# Main.net
KiCad netlist of a schematic drawn in Altium Designer
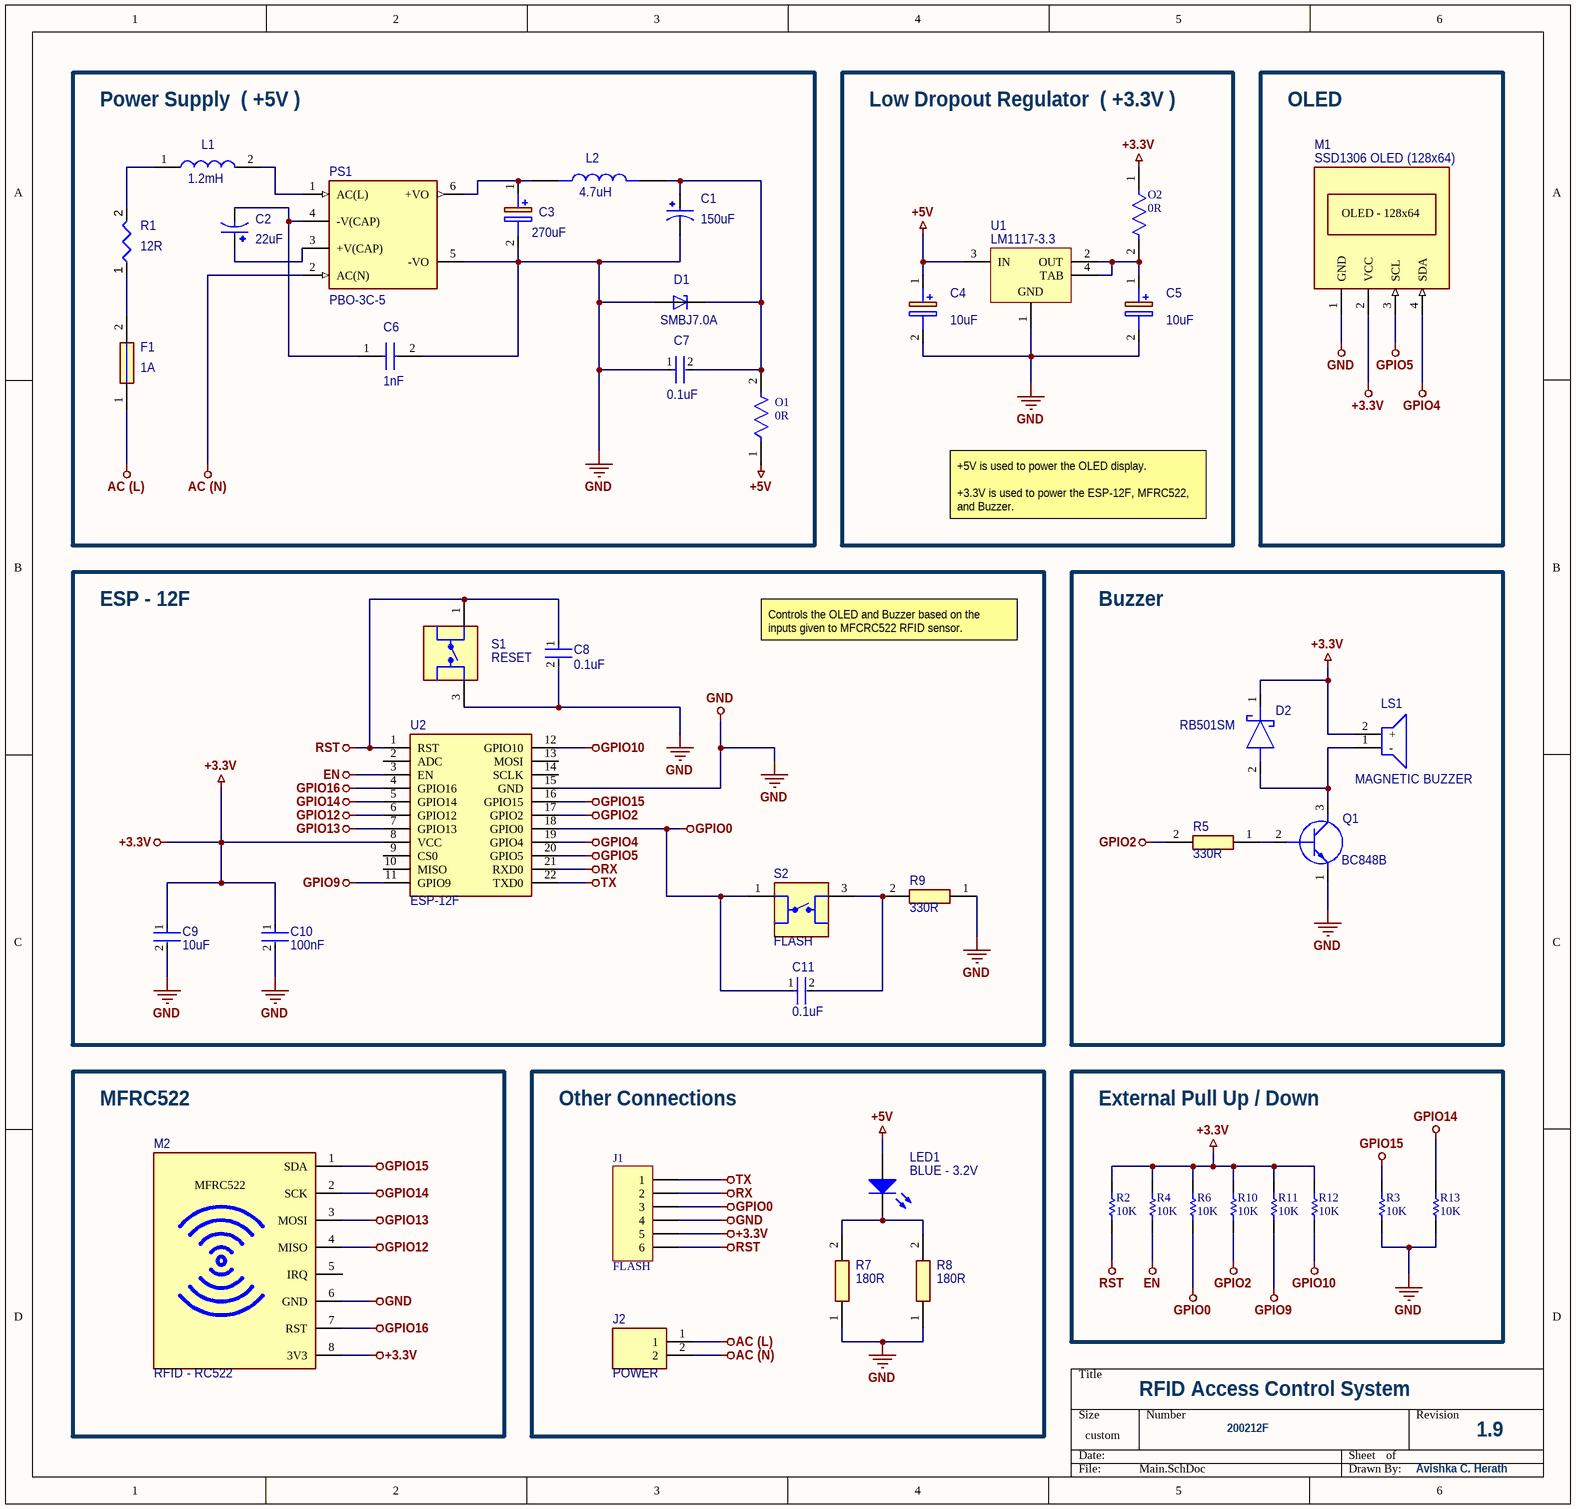
[diagram p0: Main.SchDoc]

(export (version "E")
  (design (tool "Eeschema 10.0.6"))
  (components
    (comp (ref "C1")
      (value "150uF")
      (footprint "CAPPRD500W60D800H1150")
      (description "FR-A")
      (fields (field (name "MF") "{'manufacturer': u'Panasonic'}") (field (name "MP") "UHE1V151MPD1TD"))
      (libsource (lib "SnapEDA_Library") (part "EEUFR1V221B"))
    )
    (comp (ref "C2")
      (value "22uF")
      (footprint "CAPPRD750W80D1600H2500")
      (description "Aluminum Electrolytic Capacitors - Radial Leaded")
      (fields (field (name "MF") "Nichicon") (field (name "MP") "UVR2W220MHD"))
      (libsource (lib "SnapEDA_Library") (part "EEUTP1E272B"))
    )
    (comp (ref "C3")
      (value "270uF")
      (footprint "CAPPRD250W65D630H900")
      (description "Aluminum Organic Polymer Capacitors")
      (fields
        (field (name "MANUFACTURER_PART_NUMBER") "A750EM277M1CAAE015")
        (field (name "MOUSER PART NUMBER") "667-6SEPC560MW+TSS")
      )
      (libsource (lib "SamacSys") (part "6SEPC560MW+TSS"))
    )
    (comp (ref "C4")
      (value "10uF")
      (footprint "SamacSys:T491B")
      (description "Capacitor Polarised")
      (fields
        (field (name "MANUFACTURER_PART_NUMBER") "T491B106M010AT")
        (field (name "MOUSER PART NUMBER") "80-T491B106M010")
      )
      (libsource (lib "*") (part "T491B106M010AT"))
    )
    (comp (ref "C5")
      (value "10uF")
      (footprint "SamacSys:T491B")
      (description "Capacitor Polarised")
      (fields
        (field (name "MANUFACTURER_PART_NUMBER") "T491B106M010AT")
        (field (name "MOUSER PART NUMBER") "80-T491B106M010")
      )
      (libsource (lib "*") (part "T491B106M010AT"))
    )
    (comp (ref "C6")
      (value "1nF")
      (footprint "SamacSys:B32529C8102J")
      (description "Capacitor")
      (fields
        (field (name "MANUFACTURER_PART_NUMBER") "B32529C8102J")
        (field (name "MOUSER PART NUMBER") "871-B32529C8102J")
      )
      (libsource (lib "*") (part "B32529C8102J"))
    )
    (comp (ref "C7")
      (value "0.1uF")
      (footprint "FP-CL10-0_1-MFG")
      (description "CAP CER 0.1UF 50V X7R 0603")
      (fields
        (field (name "MANUFACTURER") "Samsung Electro-Mechanics America, Inc")
        (field (name "MANUFACTURER PART NUMBER") "CL10B104JB8NNNC")
      )
      (libsource (lib "Altium Content Vault") (part "b4654b650e69147ec39a6b967a45e02"))
    )
    (comp (ref "C8")
      (value "0.1uF")
      (footprint "FP-CL10-0_1-MFG")
      (description "CAP CER 0.1UF 50V X7R 0603")
      (fields
        (field (name "MANUFACTURER") "Samsung Electro-Mechanics America, Inc")
        (field (name "MANUFACTURER PART NUMBER") "CL10B104JB8NNNC")
      )
      (libsource (lib "Altium Content Vault") (part "b4654b650e69147ec39a6b967a45e02"))
    )
    (comp (ref "C9")
      (value "10uF")
      (footprint "FP-CL21-IPC_B")
      (description "CL21 Series 0805 10uF 16V ±10% Tolerance X5R Multilayer Ceramic Chip Capacitor")
      (fields (field (name "VOLTAGE") "16V") (field (name "TOLERANCE") "10%"))
      (libsource (lib "Altium Content Vault") (part "b4654b650e69147ec39a6b967a45e02"))
    )
    (comp (ref "C10")
      (value "100nF")
      (footprint "FP-CL10-0_1-MFG")
      (description "CAP CER 0.1UF 50V X7R 0603")
      (fields
        (field (name "MANUFACTURER") "Samsung Electro-Mechanics America, Inc")
        (field (name "MANUFACTURER PART NUMBER") "CL10B104JB8NNNC")
      )
      (libsource (lib "Altium Content Vault") (part "b4654b650e69147ec39a6b967a45e02"))
    )
    (comp (ref "C11")
      (value "0.1uF")
      (footprint "FP-CL10-0_1-MFG")
      (description "CAP CER 0.1UF 50V X7R 0603")
      (fields
        (field (name "MANUFACTURER") "Samsung Electro-Mechanics America, Inc")
        (field (name "MANUFACTURER PART NUMBER") "CL10B104JB8NNNC")
      )
      (libsource (lib "Altium Content Vault") (part "b4654b650e69147ec39a6b967a45e02"))
    )
    (comp (ref "D1")
      (value "SMBJ7.0A")
      (footprint "DIOM4336X265N")
      (fields (field (name "MF") "{'manufacturer': u'Littelfuse'}"))
      (libsource (lib "SnapEDA_Library") (part "SMBJ7.0A"))
    )
    (comp (ref "D2")
      (value "RB501SM")
      (footprint "SamacSys:RB501SM30FHT2R")
      (description "Schottky Diode")
      (fields
        (field (name "MANUFACTURER_PART_NUMBER") "RB501SM-30FHT2R")
        (field (name "MOUSER PART NUMBER") "755-RB501SM-30FHT2R")
      )
      (libsource (lib "*") (part "RB501SM-30FHT2R"))
    )
    (comp (ref "F1")
      (value "1A")
      (footprint "SS5H1AAPH")
      (description "Fuse")
      (fields
        (field (name "MOUSER PART NUMBER") "504-SS-5H-1A-APH")
        (field (name "MANUFACTURER_PART_NUMBER") "SS-5H-1A-APH")
      )
      (libsource (lib "University of Moratuwa") (part "SS-5H-1A-APH"))
    )
    (comp (ref "J1")
      (value "FLASH")
      (footprint "My_1X06")
      (description "Header, 6-Pin")
      (fields (field (name "ASID PART NUMBER") "Header 6-AS"))
      (libsource (lib "Mylib+Rev+4") (part "Header 6"))
    )
    (comp (ref "J2")
      (value "POWER")
      (footprint "SamacSys:TB00250002BE")
      (description "Connector")
      (fields
        (field (name "MANUFACTURER_PART_NUMBER") "TB002-500-02BE")
        (field (name "MOUSER PART NUMBER") "490-TB002-500-02BE")
      )
      (libsource (lib "*") (part "TB002-500-02BE"))
    )
    (comp (ref "L1")
      (value "1.2mH")
      (footprint "SamacSys:RLB9012122KL")
      (description "Inductor")
      (fields
        (field (name "MANUFACTURER_PART_NUMBER") "RLB9012-122KL")
        (field (name "MOUSER PART NUMBER") "652-RLB9012-122KL")
      )
      (libsource (lib "*") (part "RLB9012-122KL"))
    )
    (comp (ref "L2")
      (value "4.7uH")
      (footprint "IND_ASPI-0615FS-4R7M-T2")
      (fields (field (name "MF") "{'manufacturer': u'Abracon'}") (field (name "MP") "ASPI-0615FS-4R7M-T2"))
      (libsource (lib "SnapEDA_Library") (part "ASPI-0615FS-4R7M-T2"))
    )
    (comp (ref "LED1")
      (value "BLUE - 3.2V")
      (footprint "3528")
      (description "SMD mono-color Top LED, WL-SMTW, Blue")
      (fields (field (name "PARTNUMBER") "150141BS73100") (field (name "MANUFACTURER") "Wuerth Elektronik"))
      (libsource (lib "Altium Content Vault") (part "WE-LED_K1A2-2"))
    )
    (comp (ref "LS1")
      (value "MAGNETIC BUZZER")
      (footprint "SamacSys:CMI1295IC0385T")
      (description "Loudspeaker or Buzzer")
      (fields
        (field (name "MANUFACTURER_PART_NUMBER") "CMI-1295IC-0385T")
        (field (name "MOUSER PART NUMBER") "490-CMI-1295IC-0385T")
      )
      (libsource (lib "*") (part "CMI-1295IC-0385T"))
    )
    (comp (ref "M1")
      (value "SSD1306 OLED (128x64)")
      (footprint "SSD1306 OLED (128x64)-Footprint-1")
      (libsource (lib "University of Moratuwa") (part "SSD1306 OLED (128x64)"))
    )
    (comp (ref "M2")
      (value "RFID - RC522")
      (footprint "RFID - RC522-Footprint-1")
      (libsource (lib "University of Moratuwa") (part "RFID - RC522"))
    )
    (comp (ref "O1")
      (value "0R")
      (footprint "FP-RC0805-MFG")
      (description "RES SMD 0 OHM JUMPER 1/8W 0805")
      (fields
        (field (name "OCTOPART") "https://octopart.com/rc0805fr-070rl-yageo-9293404")
        (field (name "MANUFACTURER") "Yageo")
      )
      (libsource (lib "Altium Content Vault") (part "1029c3af85768c4190bb7ad29bc67b5"))
    )
    (comp (ref "O2")
      (value "0R")
      (footprint "FP-RC0805-MFG")
      (description "RES SMD 0 OHM JUMPER 1/8W 0805")
      (fields
        (field (name "OCTOPART") "https://octopart.com/rc0805fr-070rl-yageo-9293404")
        (field (name "MANUFACTURER") "Yageo")
      )
      (libsource (lib "Altium Content Vault") (part "1029c3af85768c4190bb7ad29bc67b5"))
    )
    (comp (ref "PS1")
      (value "PBO-3C-5")
      (footprint "CONV_PBO-3C-5")
      (fields (field (name "MF") "{'manufacturer': u'CUI'}"))
      (libsource (lib "SnapEDA_Library") (part "PBO-3C-5"))
    )
    (comp (ref "Q1")
      (value "BC848B")
      (footprint "SamacSys:SOT95P240X120-3N")
      (description "Transistor BJT NPN")
      (fields
        (field (name "MANUFACTURER_PART_NUMBER") "BC848BHZGT116")
        (field (name "MOUSER PART NUMBER") "755-BC848BHZGT116")
      )
      (libsource (lib "*") (part "BC848BHZGT116"))
    )
    (comp (ref "R1")
      (value "12R")
      (footprint "WA84-12RJI-Footprint-1")
      (libsource (lib "University of Moratuwa") (part "WA84-12RJI"))
    )
    (comp (ref "R2")
      (value "10K")
      (footprint "RESC2013X60X35ML10T20")
      (description "Res Thick Film 0805 10K Ohm 1% 0.125W(1/8W) +/-100ppm/C Epoxy Pad SMD T/R")
      (libsource (lib "University of Moratuwa") (part "RES-2"))
    )
    (comp (ref "R3")
      (value "10K")
      (footprint "RESC2013X60X35ML10T20")
      (description "Res Thick Film 0805 10K Ohm 1% 0.125W(1/8W) +/-100ppm/C Epoxy Pad SMD T/R")
      (libsource (lib "University of Moratuwa") (part "RES-2"))
    )
    (comp (ref "R4")
      (value "10K")
      (footprint "RESC2013X60X35ML10T20")
      (description "Res Thick Film 0805 10K Ohm 1% 0.125W(1/8W) +/-100ppm/C Epoxy Pad SMD T/R")
      (libsource (lib "University of Moratuwa") (part "RES-2"))
    )
    (comp (ref "R5")
      (value "330R")
      (footprint "SamacSys:RESC2012X60N")
      (description "Resistor")
      (fields
        (field (name "MANUFACTURER_PART_NUMBER") "RC0805FR-07330RL")
        (field (name "MOUSER PART NUMBER") "603-RC0805FR-07330RL")
      )
      (libsource (lib "*") (part "RC0805FR-07330RL"))
    )
    (comp (ref "R6")
      (value "10K")
      (footprint "RESC2013X60X35ML10T20")
      (description "Res Thick Film 0805 10K Ohm 1% 0.125W(1/8W) +/-100ppm/C Epoxy Pad SMD T/R")
      (libsource (lib "University of Moratuwa") (part "RES-2"))
    )
    (comp (ref "R7")
      (value "180R")
      (footprint "SamacSys:RESC2012X60N")
      (description "Resistor")
      (fields
        (field (name "MANUFACTURER_PART_NUMBER") "RC0805FR-07180RL")
        (field (name "MOUSER PART NUMBER") "603-RC0805FR-07180RL")
      )
      (libsource (lib "*") (part "RC0805FR-07180RL"))
    )
    (comp (ref "R8")
      (value "180R")
      (footprint "SamacSys:RESC2012X60N")
      (description "Resistor")
      (fields
        (field (name "MANUFACTURER_PART_NUMBER") "RC0805FR-07180RL")
        (field (name "MOUSER PART NUMBER") "603-RC0805FR-07180RL")
      )
      (libsource (lib "*") (part "RC0805FR-07180RL"))
    )
    (comp (ref "R9")
      (value "330R")
      (footprint "SamacSys:RESC2012X60N")
      (description "Resistor")
      (fields
        (field (name "MANUFACTURER_PART_NUMBER") "RC0805FR-07330RL")
        (field (name "MOUSER PART NUMBER") "603-RC0805FR-07330RL")
      )
      (libsource (lib "*") (part "RC0805FR-07330RL"))
    )
    (comp (ref "R10")
      (value "10K")
      (footprint "RESC2013X60X35ML10T20")
      (description "Res Thick Film 0805 10K Ohm 1% 0.125W(1/8W) +/-100ppm/C Epoxy Pad SMD T/R")
      (libsource (lib "University of Moratuwa") (part "RES-2"))
    )
    (comp (ref "R11")
      (value "10K")
      (footprint "RESC2013X60X35ML10T20")
      (description "Res Thick Film 0805 10K Ohm 1% 0.125W(1/8W) +/-100ppm/C Epoxy Pad SMD T/R")
      (libsource (lib "University of Moratuwa") (part "RES-2"))
    )
    (comp (ref "R12")
      (value "10K")
      (footprint "RESC2013X60X35ML10T20")
      (description "Res Thick Film 0805 10K Ohm 1% 0.125W(1/8W) +/-100ppm/C Epoxy Pad SMD T/R")
      (libsource (lib "University of Moratuwa") (part "RES-2"))
    )
    (comp (ref "R13")
      (value "10K")
      (footprint "RESC2013X60X35ML10T20")
      (description "Res Thick Film 0805 10K Ohm 1% 0.125W(1/8W) +/-100ppm/C Epoxy Pad SMD T/R")
      (libsource (lib "University of Moratuwa") (part "RES-2"))
    )
    (comp (ref "S1")
      (value "RESET")
      (footprint "SW_PTS525SM15SMTR2LFS")
      (description "Tactile Switch SPST-NO Top Actuated Surface Mount")
      (fields (field (name "MP") "PTS525SM15SMTR2 LFS") (field (name "MF") "C&K"))
      (libsource (lib "") (part "PTS525SM15SMTR2LFS_1"))
    )
    (comp (ref "S2")
      (value "FLASH")
      (footprint "SW_PTS525SM15SMTR2LFS")
      (description "Tactile Switch SPST-NO Top Actuated Surface Mount")
      (fields (field (name "MP") "PTS525SM15SMTR2 LFS") (field (name "MF") "C&K"))
      (libsource (lib "University of Moratuwa") (part "PTS525SM15SMTR2LFS"))
    )
    (comp (ref "U1")
      (value "LM1117-3.3")
      (footprint "DCY0004A_L")
      (description "800mA Low-Dropout Linear Regulator, 4-pin SOT-223, Pb-Free")
      (fields
        (field (name "PARTNUMBER") "LM1117MPX-3.3/NOPB")
        (field (name "MANUFACTURER") "Texas Instruments")
      )
      (libsource (lib "Altium Content Vault") (part "PM-REG-LM1086-SOT4"))
    )
    (comp (ref "U2")
      (value "ESP-12F")
      (footprint "SamacSys:esp12f")
      (description "Integrated Circuit")
      (libsource (lib "*") (part "esp-12f"))
    )
  )
  (nets
    (net (code "1") (name "+3.3V") (class "Default")
      (node (ref "C10") (pin "1") (pinfunction "1_1") (pintype "passive"))
      (node (ref "C9") (pin "1") (pinfunction "1_1") (pintype "passive"))
      (node (ref "D2") (pin "1") (pinfunction "K_1") (pintype "passive"))
      (node (ref "J1") (pin "5") (pinfunction "5_5") (pintype "passive"))
      (node (ref "LS1") (pin "2") (pinfunction "+_2") (pintype "passive"))
      (node (ref "M1") (pin "2") (pinfunction "VCC_2") (pintype "power_in"))
      (node (ref "M2") (pin "8") (pinfunction "3V3_8") (pintype "passive"))
      (node (ref "O2") (pin "1") (pinfunction "1_1") (pintype "passive"))
      (node (ref "R10") (pin "2") (pinfunction "2_2") (pintype "passive"))
      (node (ref "R11") (pin "2") (pinfunction "2_2") (pintype "passive"))
      (node (ref "R12") (pin "2") (pinfunction "2_2") (pintype "passive"))
      (node (ref "R2") (pin "1") (pinfunction "1_1") (pintype "passive"))
      (node (ref "R4") (pin "1") (pinfunction "1_1") (pintype "passive"))
      (node (ref "R6") (pin "2") (pinfunction "2_2") (pintype "passive"))
      (node (ref "U2") (pin "8") (pinfunction "VCC_8") (pintype "passive"))
    )
    (net (code "2") (name "+5V") (class "Default")
      (node (ref "C4") (pin "1") (pinfunction "+_1") (pintype "passive"))
      (node (ref "LED1") (pin "2") (pinfunction "A_2") (pintype "passive"))
      (node (ref "O1") (pin "1") (pinfunction "1_1") (pintype "passive"))
      (node (ref "U1") (pin "3") (pinfunction "IN_3") (pintype "power_in"))
    )
    (net (code "3") (name "AC (L)") (class "Default")
      (node (ref "F1") (pin "1") (pinfunction "1_1") (pintype "passive"))
      (node (ref "J2") (pin "1") (pinfunction "1_1") (pintype "passive"))
    )
    (net (code "4") (name "AC (N)") (class "Default")
      (node (ref "J2") (pin "2") (pinfunction "2_2") (pintype "passive"))
      (node (ref "PS1") (pin "2") (pinfunction "AC(N)_2") (pintype "input"))
    )
    (net (code "5") (name "EN") (class "Default")
      (node (ref "R4") (pin "2") (pinfunction "2_2") (pintype "passive"))
      (node (ref "U2") (pin "3") (pinfunction "EN_3") (pintype "passive"))
    )
    (net (code "6") (name "GND") (class "Default")
      (node (ref "C1") (pin "N") (pinfunction "N_N") (pintype "passive"))
      (node (ref "C10") (pin "2") (pinfunction "2_2") (pintype "passive"))
      (node (ref "C3") (pin "2") (pinfunction "-_2") (pintype "passive"))
      (node (ref "C4") (pin "2") (pinfunction "-_2") (pintype "passive"))
      (node (ref "C5") (pin "2") (pinfunction "-_2") (pintype "passive"))
      (node (ref "C6") (pin "2") (pinfunction "2_2") (pintype "passive"))
      (node (ref "C7") (pin "1") (pinfunction "1_1") (pintype "passive"))
      (node (ref "C8") (pin "2") (pinfunction "2_2") (pintype "passive"))
      (node (ref "C9") (pin "2") (pinfunction "2_2") (pintype "passive"))
      (node (ref "D1") (pin "A") (pinfunction "A_A") (pintype "passive"))
      (node (ref "J1") (pin "4") (pinfunction "4_4") (pintype "passive"))
      (node (ref "M1") (pin "1") (pinfunction "GND_1") (pintype "power_in"))
      (node (ref "M2") (pin "6") (pinfunction "GND_6") (pintype "passive"))
      (node (ref "PS1") (pin "5") (pinfunction "-VO_5") (pintype "passive"))
      (node (ref "Q1") (pin "1") (pinfunction "E_1") (pintype "passive"))
      (node (ref "R13") (pin "2") (pinfunction "2_2") (pintype "passive"))
      (node (ref "R3") (pin "2") (pinfunction "2_2") (pintype "passive"))
      (node (ref "R7") (pin "1") (pinfunction "1_1") (pintype "passive"))
      (node (ref "R8") (pin "1") (pinfunction "1_1") (pintype "passive"))
      (node (ref "R9") (pin "1") (pinfunction "1_1") (pintype "passive"))
      (node (ref "S1") (pin "3") (pinfunction "3_3") (pintype "passive"))
      (node (ref "U1") (pin "1") (pinfunction "GND_1") (pintype "power_in"))
      (node (ref "U2") (pin "15") (pinfunction "GND_15") (pintype "passive"))
    )
    (net (code "7") (name "GPIO0") (class "Default")
      (node (ref "C11") (pin "1") (pinfunction "1_1") (pintype "passive"))
      (node (ref "J1") (pin "3") (pinfunction "3_3") (pintype "passive"))
      (node (ref "R6") (pin "1") (pinfunction "1_1") (pintype "passive"))
      (node (ref "S2") (pin "1") (pinfunction "1_1") (pintype "passive"))
      (node (ref "U2") (pin "18") (pinfunction "GPIO0_18") (pintype "passive"))
    )
    (net (code "8") (name "GPIO2") (class "Default")
      (node (ref "R10") (pin "1") (pinfunction "1_1") (pintype "passive"))
      (node (ref "R5") (pin "2") (pinfunction "2_2") (pintype "passive"))
      (node (ref "U2") (pin "17") (pinfunction "GPIO2_17") (pintype "passive"))
    )
    (net (code "9") (name "GPIO4") (class "Default")
      (node (ref "M1") (pin "4") (pinfunction "SDA_4") (pintype "input"))
      (node (ref "U2") (pin "19") (pinfunction "GPIO4_19") (pintype "passive"))
    )
    (net (code "10") (name "GPIO5") (class "Default")
      (node (ref "M1") (pin "3") (pinfunction "SCL_3") (pintype "input"))
      (node (ref "U2") (pin "20") (pinfunction "GPIO5_20") (pintype "passive"))
    )
    (net (code "11") (name "GPIO9") (class "Default")
      (node (ref "R11") (pin "1") (pinfunction "1_1") (pintype "passive"))
      (node (ref "U2") (pin "11") (pinfunction "GPIO9_11") (pintype "passive"))
    )
    (net (code "12") (name "GPIO10") (class "Default")
      (node (ref "R12") (pin "1") (pinfunction "1_1") (pintype "passive"))
      (node (ref "U2") (pin "12") (pinfunction "GPIO10_12") (pintype "passive"))
    )
    (net (code "13") (name "GPIO12") (class "Default")
      (node (ref "M2") (pin "4") (pinfunction "MISO_4") (pintype "passive"))
      (node (ref "U2") (pin "6") (pinfunction "GPIO12_6") (pintype "passive"))
    )
    (net (code "14") (name "GPIO13") (class "Default")
      (node (ref "M2") (pin "3") (pinfunction "MOSI_3") (pintype "passive"))
      (node (ref "U2") (pin "7") (pinfunction "GPIO13_7") (pintype "passive"))
    )
    (net (code "15") (name "GPIO14") (class "Default")
      (node (ref "M2") (pin "2") (pinfunction "SCK_2") (pintype "passive"))
      (node (ref "R13") (pin "1") (pinfunction "1_1") (pintype "passive"))
      (node (ref "U2") (pin "5") (pinfunction "GPIO14_5") (pintype "passive"))
    )
    (net (code "16") (name "GPIO15") (class "Default")
      (node (ref "M2") (pin "1") (pinfunction "SDA_1") (pintype "passive"))
      (node (ref "R3") (pin "1") (pinfunction "1_1") (pintype "passive"))
      (node (ref "U2") (pin "16") (pinfunction "GPIO15_16") (pintype "passive"))
    )
    (net (code "17") (name "GPIO16") (class "Default")
      (node (ref "M2") (pin "7") (pinfunction "RST_7") (pintype "passive"))
      (node (ref "U2") (pin "4") (pinfunction "GPIO16_4") (pintype "passive"))
    )
    (net (code "18") (name "Net-(C1-PadP)") (class "Default")
      (node (ref "C1") (pin "P") (pinfunction "P_P") (pintype "passive"))
      (node (ref "C7") (pin "2") (pinfunction "2_2") (pintype "passive"))
      (node (ref "D1") (pin "C") (pinfunction "C_C") (pintype "passive"))
      (node (ref "L2") (pin "2") (pinfunction "2_2") (pintype "passive"))
      (node (ref "O1") (pin "2") (pinfunction "2_2") (pintype "passive"))
    )
    (net (code "19") (name "Net-(C2-PadN)") (class "Default")
      (node (ref "C2") (pin "N") (pinfunction "N_N") (pintype "passive"))
      (node (ref "C6") (pin "1") (pinfunction "1_1") (pintype "passive"))
      (node (ref "PS1") (pin "4") (pinfunction "-V(CAP)_4") (pintype "passive"))
    )
    (net (code "20") (name "Net-(C3-+)") (class "Default")
      (node (ref "C3") (pin "1") (pinfunction "+_1") (pintype "passive"))
      (node (ref "L2") (pin "1") (pinfunction "1_1") (pintype "passive"))
      (node (ref "PS1") (pin "6") (pinfunction "+VO_6") (pintype "output"))
    )
    (net (code "21") (name "Net-(C5-+)") (class "Default")
      (node (ref "C5") (pin "1") (pinfunction "+_1") (pintype "passive"))
      (node (ref "O2") (pin "2") (pinfunction "2_2") (pintype "passive"))
      (node (ref "U1") (pin "2") (pinfunction "OUT_2") (pintype "power_in"))
      (node (ref "U1") (pin "4") (pinfunction "TAB_4") (pintype "power_in"))
    )
    (net (code "22") (name "Net-(C11-Pad2)") (class "Default")
      (node (ref "C11") (pin "2") (pinfunction "2_2") (pintype "passive"))
      (node (ref "R9") (pin "2") (pinfunction "2_2") (pintype "passive"))
      (node (ref "S2") (pin "3") (pinfunction "3_3") (pintype "passive"))
    )
    (net (code "23") (name "Net-(D2-A)") (class "Default")
      (node (ref "D2") (pin "2") (pinfunction "A_2") (pintype "passive"))
      (node (ref "LS1") (pin "1") (pinfunction "-_1") (pintype "passive"))
      (node (ref "Q1") (pin "3") (pinfunction "C_3") (pintype "passive"))
    )
    (net (code "24") (name "Net-(F1-Pad2)") (class "Default")
      (node (ref "F1") (pin "2") (pinfunction "2_2") (pintype "passive"))
      (node (ref "R1") (pin "1") (pinfunction "1_1") (pintype "passive"))
    )
    (net (code "25") (name "Net-(L1-Pad1)") (class "Default")
      (node (ref "L1") (pin "1") (pinfunction "1_1") (pintype "passive"))
      (node (ref "R1") (pin "2") (pinfunction "2_2") (pintype "passive"))
    )
    (net (code "26") (name "Net-(LED1-K)") (class "Default")
      (node (ref "LED1") (pin "1") (pinfunction "K_1") (pintype "passive"))
      (node (ref "R7") (pin "2") (pinfunction "2_2") (pintype "passive"))
      (node (ref "R8") (pin "2") (pinfunction "2_2") (pintype "passive"))
    )
    (net (code "27") (name "Net-(PS1-+V(CAP))") (class "Default")
      (node (ref "C2") (pin "P") (pinfunction "P_P") (pintype "passive"))
      (node (ref "PS1") (pin "3") (pinfunction "+V(CAP)_3") (pintype "passive"))
    )
    (net (code "28") (name "Net-(PS1-AC(L))") (class "Default")
      (node (ref "L1") (pin "2") (pinfunction "2_2") (pintype "passive"))
      (node (ref "PS1") (pin "1") (pinfunction "AC(L)_1") (pintype "input"))
    )
    (net (code "29") (name "Net-(Q1-B)") (class "Default")
      (node (ref "Q1") (pin "2") (pinfunction "B_2") (pintype "passive"))
      (node (ref "R5") (pin "1") (pinfunction "1_1") (pintype "passive"))
    )
    (net (code "30") (name "RST") (class "Default")
      (node (ref "C8") (pin "1") (pinfunction "1_1") (pintype "passive"))
      (node (ref "J1") (pin "6") (pinfunction "6_6") (pintype "passive"))
      (node (ref "R2") (pin "2") (pinfunction "2_2") (pintype "passive"))
      (node (ref "S1") (pin "1") (pinfunction "1_1") (pintype "passive"))
      (node (ref "U2") (pin "1") (pinfunction "RST_1") (pintype "passive"))
    )
    (net (code "31") (name "RX") (class "Default")
      (node (ref "J1") (pin "2") (pinfunction "2_2") (pintype "passive"))
      (node (ref "U2") (pin "21") (pinfunction "RXD0_21") (pintype "passive"))
    )
    (net (code "32") (name "TX") (class "Default")
      (node (ref "J1") (pin "1") (pinfunction "1_1") (pintype "passive"))
      (node (ref "U2") (pin "22") (pinfunction "TXD0_22") (pintype "passive"))
    )
    (net (code "33") (name "unconnected-(M2-IRQ-Pad5)") (class "Default")
      (node (ref "M2") (pin "5") (pinfunction "IRQ_5") (pintype "passive"))
    )
    (net (code "34") (name "unconnected-(PS1--V(CAP)-Pad4_2)") (class "Default")
      (node (ref "PS1") (pin "4_2") (pinfunction "-V(CAP)_4_2") (pintype "passive"))
    )
    (net (code "35") (name "unconnected-(PS1--VO-Pad5_2)") (class "Default")
      (node (ref "PS1") (pin "5_2") (pinfunction "-VO_5_2") (pintype "output"))
    )
    (net (code "36") (name "unconnected-(S1-Pad2)") (class "Default")
      (node (ref "S1") (pin "2") (pinfunction "2_2") (pintype "passive"))
    )
    (net (code "37") (name "unconnected-(S1-Pad4)") (class "Default")
      (node (ref "S1") (pin "4") (pinfunction "4_4") (pintype "passive"))
    )
    (net (code "38") (name "unconnected-(S2-Pad2)") (class "Default")
      (node (ref "S2") (pin "2") (pinfunction "2_2") (pintype "passive"))
    )
    (net (code "39") (name "unconnected-(S2-Pad4)") (class "Default")
      (node (ref "S2") (pin "4") (pinfunction "4_4") (pintype "passive"))
    )
    (net (code "40") (name "unconnected-(U2-ADC-Pad2)") (class "Default")
      (node (ref "U2") (pin "2") (pinfunction "ADC_2") (pintype "passive"))
    )
    (net (code "41") (name "unconnected-(U2-CS0-Pad9)") (class "Default")
      (node (ref "U2") (pin "9") (pinfunction "CS0_9") (pintype "passive"))
    )
    (net (code "42") (name "unconnected-(U2-MISO-Pad10)") (class "Default")
      (node (ref "U2") (pin "10") (pinfunction "MISO_10") (pintype "passive"))
    )
    (net (code "43") (name "unconnected-(U2-MOSI-Pad13)") (class "Default")
      (node (ref "U2") (pin "13") (pinfunction "MOSI_13") (pintype "passive"))
    )
    (net (code "44") (name "unconnected-(U2-SCLK-Pad14)") (class "Default")
      (node (ref "U2") (pin "14") (pinfunction "SCLK_14") (pintype "passive"))
    )
  )
)
